# myNucSatellite.net
KiCad netlist of a schematic drawn in EAGLE
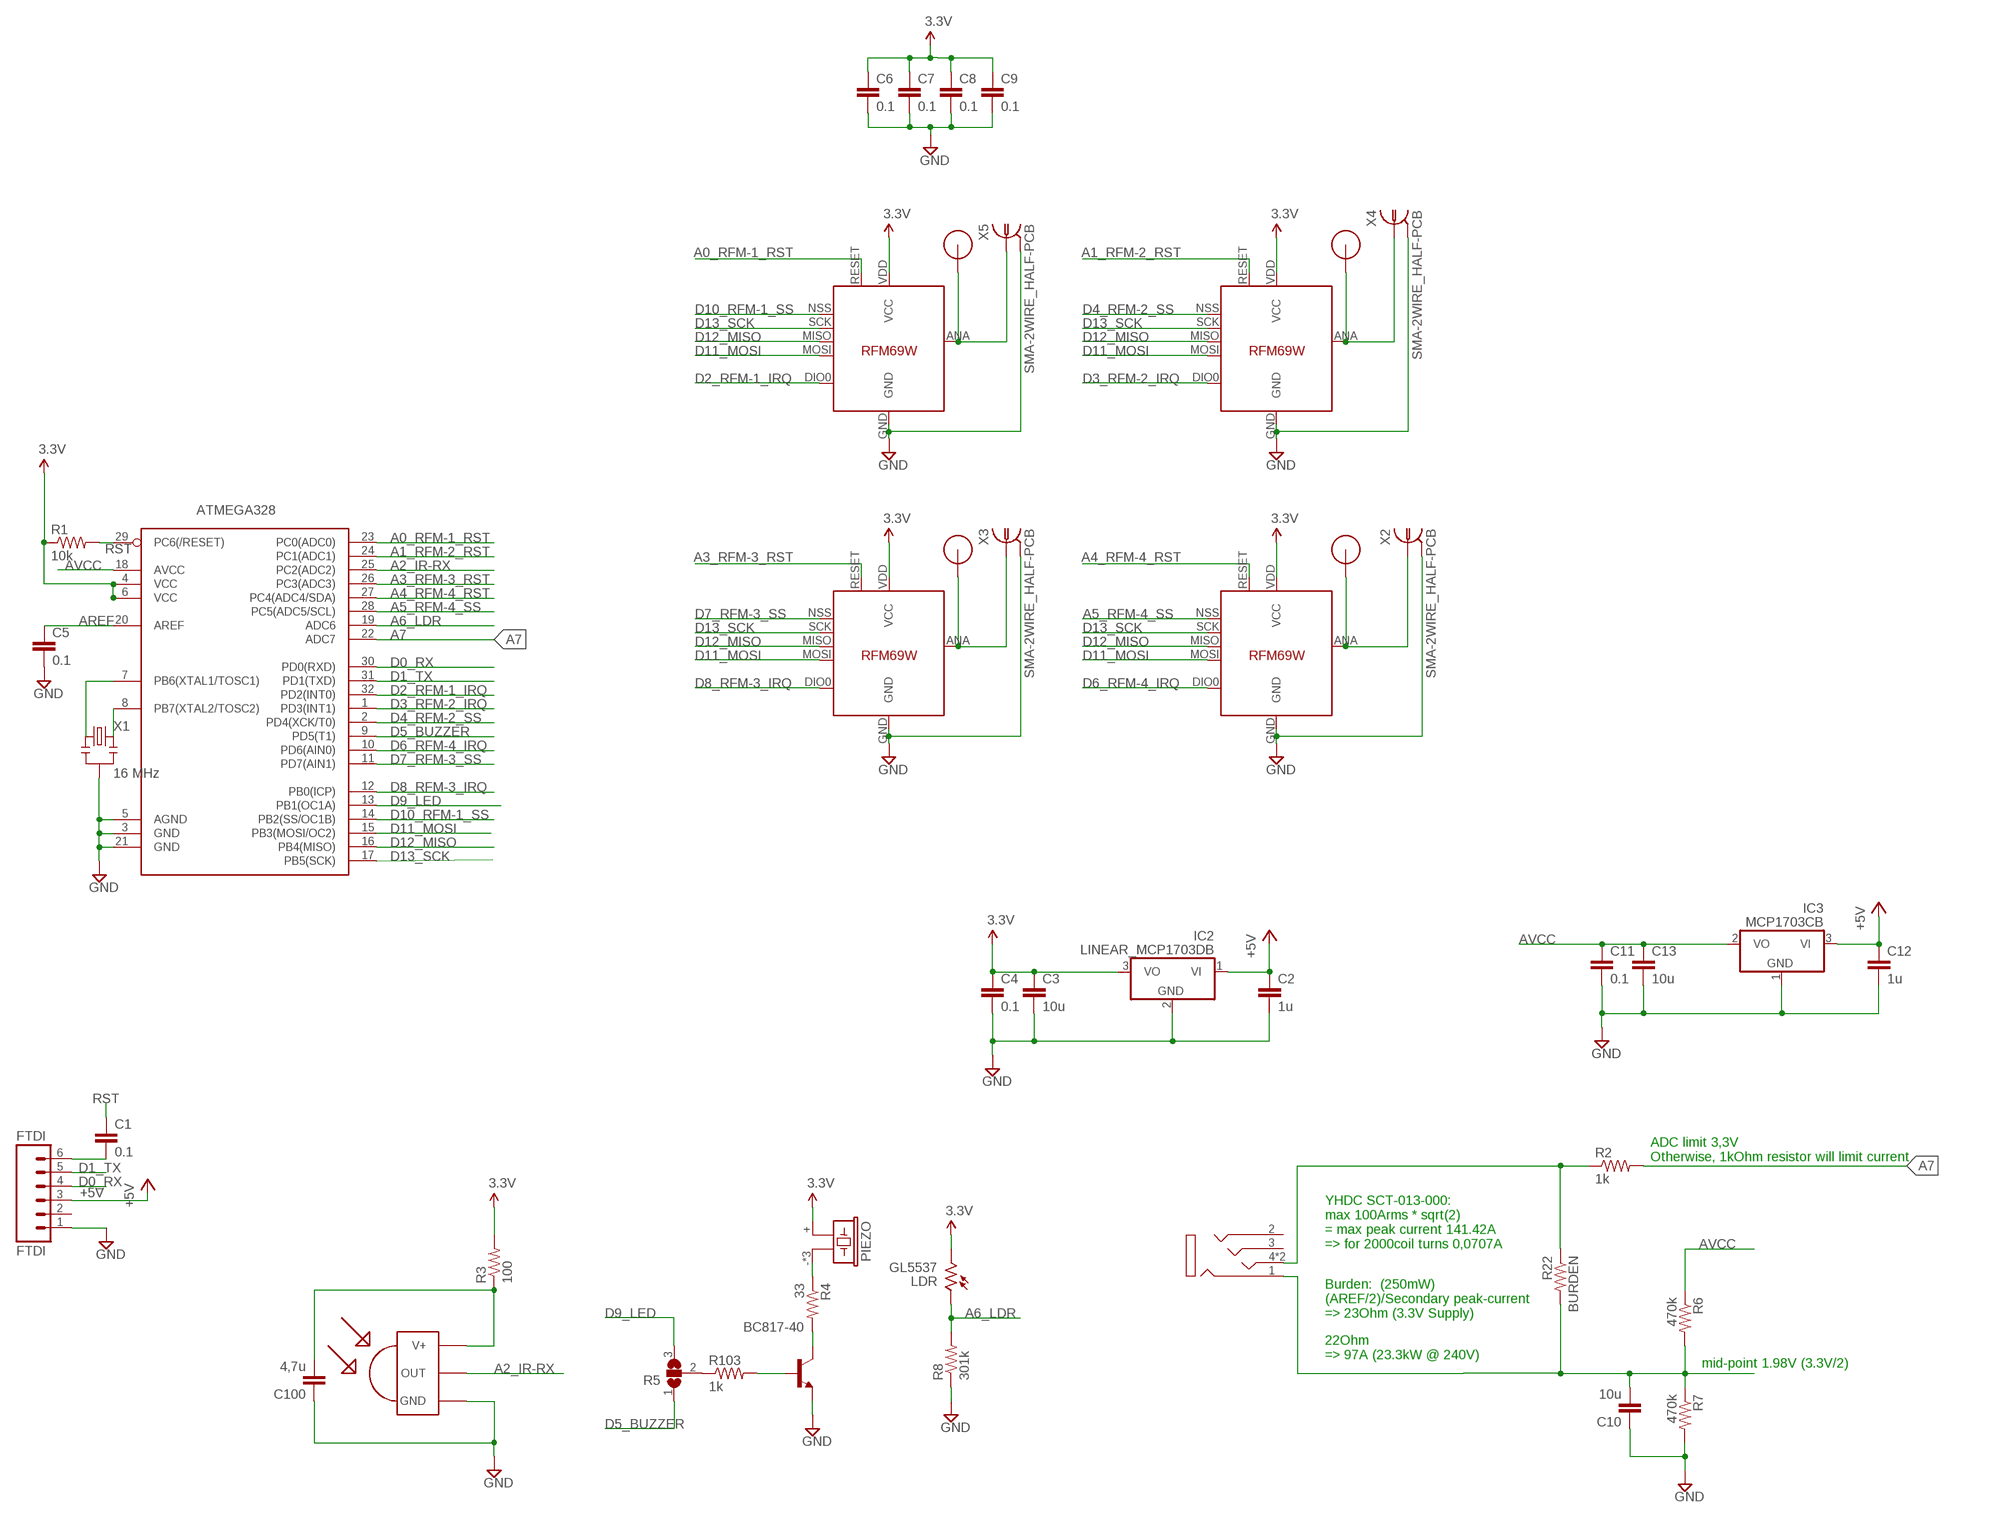
[diagram p0: schematic, sheet 1]

(export (version "E")
  (design (tool "Eeschema 10.0.6"))
  (components
    (comp (ref "ATMEGA328")
      (value "ATMega-328")
      (footprint "eagle-import:TQFP32-08")
      (libsource (lib "eagle-import") (part "ATMEGA168/328TQFP32"))
    )
    (comp (ref "BC817-40")
      (value "BC817-40-NPN-SOT23-BEC")
      (footprint "eagle-import:SOT23-BEC")
      (libsource (lib "eagle-import") (part "-NPN-SOT23-BECBC817-40"))
    )
    (comp (ref "BURDEN")
      (value "R22")
      (footprint "eagle-import:R0805")
      (libsource (lib "eagle-import") (part "R-US_R0805"))
    )
    (comp (ref "C1")
      (value "0.1")
      (footprint "eagle-import:0603-CAP")
      (libsource (lib "eagle-import") (part "CAP0603-CAP"))
    )
    (comp (ref "C2")
      (value "1u")
      (footprint "eagle-import:0603-CAP")
      (libsource (lib "eagle-import") (part "CAP0603-CAP"))
    )
    (comp (ref "C3")
      (value "10u")
      (footprint "eagle-import:0805-CAP")
      (libsource (lib "eagle-import") (part "myLib_CAP0805-CAP"))
    )
    (comp (ref "C4")
      (value "0.1")
      (footprint "eagle-import:0603-CAP")
      (libsource (lib "eagle-import") (part "CAP0603-CAP"))
    )
    (comp (ref "C5")
      (value "0.1")
      (footprint "eagle-import:0603-CAP")
      (libsource (lib "eagle-import") (part "CAP0603-CAP"))
    )
    (comp (ref "C6")
      (value "0.1")
      (footprint "eagle-import:0603-CAP")
      (libsource (lib "eagle-import") (part "CAP0603-CAP"))
    )
    (comp (ref "C7")
      (value "0.1")
      (footprint "eagle-import:0603-CAP")
      (libsource (lib "eagle-import") (part "CAP0603-CAP"))
    )
    (comp (ref "C8")
      (value "0.1")
      (footprint "eagle-import:0603-CAP")
      (libsource (lib "eagle-import") (part "CAP0603-CAP"))
    )
    (comp (ref "C9")
      (value "0.1")
      (footprint "eagle-import:0603-CAP")
      (libsource (lib "eagle-import") (part "CAP0603-CAP"))
    )
    (comp (ref "C10")
      (value "10u")
      (footprint "eagle-import:0603-CAP")
      (libsource (lib "eagle-import") (part "CAP0603-CAP"))
    )
    (comp (ref "C11")
      (value "0.1")
      (footprint "eagle-import:0603-CAP")
      (libsource (lib "eagle-import") (part "CAP0603-CAP"))
    )
    (comp (ref "C12")
      (value "1u")
      (footprint "eagle-import:0603-CAP")
      (libsource (lib "eagle-import") (part "CAP0603-CAP"))
    )
    (comp (ref "C13")
      (value "10u")
      (footprint "eagle-import:0805-CAP")
      (libsource (lib "eagle-import") (part "myLib_CAP0805-CAP"))
    )
    (comp (ref "C100")
      (value "4,7u")
      (footprint "eagle-import:0603-CAP")
      (libsource (lib "eagle-import") (part "CAP0603-CAP"))
    )
    (comp (ref "CT1")
      (value "1503_13")
      (footprint "eagle-import:1503-03")
      (libsource (lib "eagle-import") (part "1503_13"))
    )
    (comp (ref "FTDI")
      (value "FTDI")
      (footprint "eagle-import:1X06")
      (libsource (lib "eagle-import") (part "M06SIP"))
    )
    (comp (ref "IC2")
      (value "LINEAR_MCP1703DB")
      (footprint "eagle-import:LINEAR_SOT223")
      (libsource (lib "eagle-import") (part "LINEAR_MCP1703DB"))
    )
    (comp (ref "IC3")
      (value "MCP1703CB")
      (footprint "eagle-import:SOT23")
      (libsource (lib "eagle-import") (part "MCP1703CB"))
    )
    (comp (ref "IR-RX")
      (value "TSOP4836")
      (footprint "eagle-import:TSOP18XX")
      (libsource (lib "eagle-import") (part "TSOP4836"))
    )
    (comp (ref "LDR")
      (value "GL5537")
      (footprint "eagle-import:M9960")
      (libsource (lib "eagle-import") (part "M9960_11A"))
    )
    (comp (ref "PIEZO")
      (value "BUZZER-PIEZO_SMD")
      (footprint "eagle-import:BUZZER-PIEZO_SMD")
      (libsource (lib "eagle-import") (part "BUZZER-PIEZO_SMD"))
    )
    (comp (ref "R1")
      (value "10k")
      (footprint "eagle-import:0603-RES")
      (libsource (lib "eagle-import") (part "RESISTOR0603-RES"))
    )
    (comp (ref "R2")
      (value "1k")
      (footprint "eagle-import:0603-RES")
      (libsource (lib "eagle-import") (part "RESISTOR0603-RES"))
    )
    (comp (ref "R3")
      (value "100")
      (footprint "eagle-import:0603-RES")
      (libsource (lib "eagle-import") (part "RESISTOR0603-RES"))
    )
    (comp (ref "R4")
      (value "33")
      (footprint "eagle-import:0603-RES")
      (libsource (lib "eagle-import") (part "RESISTOR0603-RES"))
    )
    (comp (ref "R5")
      (value "SELECT0603-SELECT")
      (footprint "eagle-import:0603-SELECT")
      (libsource (lib "eagle-import") (part "SELECT0603-SELECT"))
    )
    (comp (ref "R6")
      (value "470k")
      (footprint "eagle-import:0603-RES")
      (libsource (lib "eagle-import") (part "RESISTOR0603-RES"))
    )
    (comp (ref "R7")
      (value "470k")
      (footprint "eagle-import:0603-RES")
      (libsource (lib "eagle-import") (part "RESISTOR0603-RES"))
    )
    (comp (ref "R8")
      (value "301k")
      (footprint "eagle-import:0603-RES")
      (libsource (lib "eagle-import") (part "RESISTOR0603-RES"))
    )
    (comp (ref "R103")
      (value "1k")
      (footprint "eagle-import:0603-RES")
      (libsource (lib "eagle-import") (part "RESISTOR0603-RES"))
    )
    (comp (ref "U$3")
      (value "RFM12B_ANTENNA")
      (footprint "eagle-import:RFM12B-ANTENNA")
      (libsource (lib "eagle-import") (part "RFM12B_ANTENNA"))
    )
    (comp (ref "U$4")
      (value "RFM69_MINIPADS")
      (footprint "eagle-import:RFM69W-MINPADS")
      (libsource (lib "eagle-import") (part "RFM69_MINIPADS"))
    )
    (comp (ref "U$6")
      (value "RFM12B_ANTENNA")
      (footprint "eagle-import:RFM12B-ANTENNA")
      (libsource (lib "eagle-import") (part "RFM12B_ANTENNA"))
    )
    (comp (ref "U$7")
      (value "RFM69_MINIPADS")
      (footprint "eagle-import:RFM69W-MINPADS")
      (libsource (lib "eagle-import") (part "RFM69_MINIPADS"))
    )
    (comp (ref "U$8")
      (value "RFM12B_ANTENNA")
      (footprint "eagle-import:RFM12B-ANTENNA")
      (libsource (lib "eagle-import") (part "RFM12B_ANTENNA"))
    )
    (comp (ref "U$9")
      (value "RFM69_MINIPADS")
      (footprint "eagle-import:RFM69W-MINPADS")
      (libsource (lib "eagle-import") (part "RFM69_MINIPADS"))
    )
    (comp (ref "U$10")
      (value "RFM12B_ANTENNA")
      (footprint "eagle-import:RFM12B-ANTENNA")
      (libsource (lib "eagle-import") (part "RFM12B_ANTENNA"))
    )
    (comp (ref "U$11")
      (value "RFM69_MINIPADS")
      (footprint "eagle-import:RFM69W-MINPADS")
      (libsource (lib "eagle-import") (part "RFM69_MINIPADS"))
    )
    (comp (ref "X1")
      (value "16 MHz")
      (footprint "eagle-import:RESONATOR-SMD")
      (libsource (lib "eagle-import") (part "RESONATORSMD"))
    )
    (comp (ref "X2")
      (value "SMA-2WIRE_HALF-PCB")
      (footprint "eagle-import:SMA-EDGE-HALF")
      (libsource (lib "eagle-import") (part "SMA-2WIRE_HALF-PCB"))
    )
    (comp (ref "X3")
      (value "SMA-2WIRE_HALF-PCB")
      (footprint "eagle-import:SMA-EDGE-HALF")
      (libsource (lib "eagle-import") (part "SMA-2WIRE_HALF-PCB"))
    )
    (comp (ref "X4")
      (value "SMA-2WIRE_HALF-PCB")
      (footprint "eagle-import:SMA-EDGE-HALF")
      (libsource (lib "eagle-import") (part "SMA-2WIRE_HALF-PCB"))
    )
    (comp (ref "X5")
      (value "SMA-2WIRE_HALF-PCB")
      (footprint "eagle-import:SMA-EDGE-HALF")
      (libsource (lib "eagle-import") (part "SMA-2WIRE_HALF-PCB"))
    )
  )
  (nets
    (net (code "1") (name "+5V") (class "Default")
      (node (ref "C12") (pin "1") (pinfunction "1_1") (pintype "passive"))
      (node (ref "C2") (pin "1") (pinfunction "1_1") (pintype "passive"))
      (node (ref "FTDI") (pin "3") (pinfunction "3_3") (pintype "passive"))
      (node (ref "IC2") (pin "1") (pinfunction "VI_1") (pintype "input"))
      (node (ref "IC3") (pin "3") (pinfunction "VI_3") (pintype "input"))
    )
    (net (code "2") (name "/A0_RFM-1_RST") (class "Default")
      (node (ref "ATMEGA328") (pin "23") (pinfunction "PC0(ADC0)_23") (pintype "bidirectional"))
      (node (ref "U$4") (pin "RESET") (pinfunction "RESET_RESET") (pintype "input"))
    )
    (net (code "3") (name "/A1_RFM-2_RST") (class "Default")
      (node (ref "ATMEGA328") (pin "24") (pinfunction "PC1(ADC1)_24") (pintype "bidirectional"))
      (node (ref "U$7") (pin "RESET") (pinfunction "RESET_RESET") (pintype "input"))
    )
    (net (code "4") (name "/A2_IR-RX") (class "Default")
      (node (ref "ATMEGA328") (pin "25") (pinfunction "PC2(ADC2)_25") (pintype "bidirectional"))
      (node (ref "IR-RX") (pin "OUT") (pinfunction "OUT_OUT") (pintype "bidirectional"))
    )
    (net (code "5") (name "/A3_RFM-3_RST") (class "Default")
      (node (ref "ATMEGA328") (pin "26") (pinfunction "PC3(ADC3)_26") (pintype "bidirectional"))
      (node (ref "U$9") (pin "RESET") (pinfunction "RESET_RESET") (pintype "input"))
    )
    (net (code "6") (name "/A4_RFM-4_RST") (class "Default")
      (node (ref "ATMEGA328") (pin "27") (pinfunction "PC4(ADC4/SDA)_27") (pintype "bidirectional"))
      (node (ref "U$11") (pin "RESET") (pinfunction "RESET_RESET") (pintype "input"))
    )
    (net (code "7") (name "/A5_RFM-4_SS") (class "Default")
      (node (ref "ATMEGA328") (pin "28") (pinfunction "PC5(ADC5/SCL)_28") (pintype "bidirectional"))
      (node (ref "U$11") (pin "NSS") (pinfunction "SEL_NSS") (pintype "input"))
    )
    (net (code "8") (name "/A6_LDR") (class "Default")
      (node (ref "ATMEGA328") (pin "19") (pinfunction "ADC6_19") (pintype "bidirectional"))
      (node (ref "LDR") (pin "1") (pinfunction "1_1") (pintype "passive"))
      (node (ref "R8") (pin "2") (pinfunction "2_2") (pintype "passive"))
    )
    (net (code "9") (name "/AREF") (class "Default")
      (node (ref "ATMEGA328") (pin "20") (pinfunction "AREF_20") (pintype "bidirectional"))
      (node (ref "C5") (pin "1") (pinfunction "1_1") (pintype "passive"))
    )
    (net (code "10") (name "/AVCC") (class "Default")
      (node (ref "ATMEGA328") (pin "18") (pinfunction "AVCC_18") (pintype "bidirectional"))
      (node (ref "C11") (pin "1") (pinfunction "1_1") (pintype "passive"))
      (node (ref "C13") (pin "1") (pinfunction "1_1") (pintype "passive"))
      (node (ref "IC3") (pin "2") (pinfunction "VO_2") (pintype "passive"))
      (node (ref "R6") (pin "1") (pinfunction "1_1") (pintype "passive"))
    )
    (net (code "11") (name "/D0_RX") (class "Default")
      (node (ref "ATMEGA328") (pin "30") (pinfunction "PD0(RXD)_30") (pintype "bidirectional"))
      (node (ref "FTDI") (pin "4") (pinfunction "4_4") (pintype "passive"))
    )
    (net (code "12") (name "/D1_TX") (class "Default")
      (node (ref "ATMEGA328") (pin "31") (pinfunction "PD1(TXD)_31") (pintype "bidirectional"))
      (node (ref "FTDI") (pin "5") (pinfunction "5_5") (pintype "passive"))
    )
    (net (code "13") (name "/D2_RFM-1_IRQ") (class "Default")
      (node (ref "ATMEGA328") (pin "32") (pinfunction "PD2(INT0)_32") (pintype "bidirectional"))
      (node (ref "U$4") (pin "DIO0") (pinfunction "DIO0/IRQ_DIO0") (pintype "open_collector"))
    )
    (net (code "14") (name "/D3_RFM-2_IRQ") (class "Default")
      (node (ref "ATMEGA328") (pin "1") (pinfunction "PD3(INT1)_1") (pintype "bidirectional"))
      (node (ref "U$7") (pin "DIO0") (pinfunction "DIO0/IRQ_DIO0") (pintype "open_collector"))
    )
    (net (code "15") (name "/D4_RFM-2_SS") (class "Default")
      (node (ref "ATMEGA328") (pin "2") (pinfunction "PD4(XCK/T0)_2") (pintype "bidirectional"))
      (node (ref "U$7") (pin "NSS") (pinfunction "SEL_NSS") (pintype "input"))
    )
    (net (code "16") (name "/D5_BUZZER") (class "Default")
      (node (ref "ATMEGA328") (pin "9") (pinfunction "PD5(T1)_9") (pintype "bidirectional"))
      (node (ref "R5") (pin "1") (pinfunction "1_1") (pintype "passive"))
    )
    (net (code "17") (name "/D6_RFM-4_IRQ") (class "Default")
      (node (ref "ATMEGA328") (pin "10") (pinfunction "PD6(AIN0)_10") (pintype "bidirectional"))
      (node (ref "U$11") (pin "DIO0") (pinfunction "DIO0/IRQ_DIO0") (pintype "open_collector"))
    )
    (net (code "18") (name "/D7_RFM-3_SS") (class "Default")
      (node (ref "ATMEGA328") (pin "11") (pinfunction "PD7(AIN1)_11") (pintype "bidirectional"))
      (node (ref "U$9") (pin "NSS") (pinfunction "SEL_NSS") (pintype "input"))
    )
    (net (code "19") (name "/D8_RFM-3_IRQ") (class "Default")
      (node (ref "ATMEGA328") (pin "12") (pinfunction "PB0(ICP)_12") (pintype "bidirectional"))
      (node (ref "U$9") (pin "DIO0") (pinfunction "DIO0/IRQ_DIO0") (pintype "open_collector"))
    )
    (net (code "20") (name "/D9_LED") (class "Default")
      (node (ref "ATMEGA328") (pin "13") (pinfunction "PB1(OC1A)_13") (pintype "bidirectional"))
      (node (ref "R5") (pin "3") (pinfunction "3_3") (pintype "passive"))
    )
    (net (code "21") (name "/D10_RFM-1_SS") (class "Default")
      (node (ref "ATMEGA328") (pin "14") (pinfunction "PB2(SS/OC1B)_14") (pintype "bidirectional"))
      (node (ref "U$4") (pin "NSS") (pinfunction "SEL_NSS") (pintype "input"))
    )
    (net (code "22") (name "/D11_MOSI") (class "Default")
      (node (ref "ATMEGA328") (pin "15") (pinfunction "PB3(MOSI/OC2)_15") (pintype "bidirectional"))
      (node (ref "U$11") (pin "MOSI") (pinfunction "MOSI_MOSI") (pintype "output"))
      (node (ref "U$4") (pin "MOSI") (pinfunction "MOSI_MOSI") (pintype "output"))
      (node (ref "U$7") (pin "MOSI") (pinfunction "MOSI_MOSI") (pintype "output"))
      (node (ref "U$9") (pin "MOSI") (pinfunction "MOSI_MOSI") (pintype "output"))
    )
    (net (code "23") (name "/D12_MISO") (class "Default")
      (node (ref "ATMEGA328") (pin "16") (pinfunction "PB4(MISO)_16") (pintype "bidirectional"))
      (node (ref "U$11") (pin "MISO") (pinfunction "MISO_MISO") (pintype "input"))
      (node (ref "U$4") (pin "MISO") (pinfunction "MISO_MISO") (pintype "input"))
      (node (ref "U$7") (pin "MISO") (pinfunction "MISO_MISO") (pintype "input"))
      (node (ref "U$9") (pin "MISO") (pinfunction "MISO_MISO") (pintype "input"))
    )
    (net (code "24") (name "/D13_SCK") (class "Default")
      (node (ref "ATMEGA328") (pin "17") (pinfunction "PB5(SCK)_17") (pintype "bidirectional"))
      (node (ref "U$11") (pin "SCK") (pinfunction "SCK_SCK") (pintype "input"))
      (node (ref "U$4") (pin "SCK") (pinfunction "SCK_SCK") (pintype "input"))
      (node (ref "U$7") (pin "SCK") (pinfunction "SCK_SCK") (pintype "input"))
      (node (ref "U$9") (pin "SCK") (pinfunction "SCK_SCK") (pintype "input"))
    )
    (net (code "25") (name "/RST") (class "Default")
      (node (ref "ATMEGA328") (pin "29") (pinfunction "PC6(/RESET)_29") (pintype "bidirectional"))
      (node (ref "C1") (pin "1") (pinfunction "1_1") (pintype "passive"))
      (node (ref "R1") (pin "2") (pinfunction "2_2") (pintype "passive"))
    )
    (net (code "26") (name "3.3V") (class "Default")
      (node (ref "ATMEGA328") (pin "4") (pinfunction "VCC_4") (pintype "bidirectional"))
      (node (ref "ATMEGA328") (pin "6") (pinfunction "VCC_6") (pintype "bidirectional"))
      (node (ref "C3") (pin "1") (pinfunction "1_1") (pintype "passive"))
      (node (ref "C4") (pin "1") (pinfunction "1_1") (pintype "passive"))
      (node (ref "C6") (pin "1") (pinfunction "1_1") (pintype "passive"))
      (node (ref "C7") (pin "1") (pinfunction "1_1") (pintype "passive"))
      (node (ref "C8") (pin "1") (pinfunction "1_1") (pintype "passive"))
      (node (ref "C9") (pin "1") (pinfunction "1_1") (pintype "passive"))
      (node (ref "IC2") (pin "3") (pinfunction "VO_3") (pintype "passive"))
      (node (ref "LDR") (pin "2") (pinfunction "2_2") (pintype "passive"))
      (node (ref "PIEZO") (pin "+") (pinfunction "1_+") (pintype "passive"))
      (node (ref "R1") (pin "1") (pinfunction "1_1") (pintype "passive"))
      (node (ref "R3") (pin "2") (pinfunction "2_2") (pintype "passive"))
      (node (ref "U$11") (pin "VDD") (pinfunction "VCC_VDD") (pintype "power_in"))
      (node (ref "U$4") (pin "VDD") (pinfunction "VCC_VDD") (pintype "power_in"))
      (node (ref "U$7") (pin "VDD") (pinfunction "VCC_VDD") (pintype "power_in"))
      (node (ref "U$9") (pin "VDD") (pinfunction "VCC_VDD") (pintype "power_in"))
    )
    (net (code "27") (name "A7") (class "Default")
      (node (ref "ATMEGA328") (pin "22") (pinfunction "ADC7_22") (pintype "bidirectional"))
      (node (ref "R2") (pin "2") (pinfunction "2_2") (pintype "passive"))
    )
    (net (code "28") (name "GND") (class "Default")
      (node (ref "ATMEGA328") (pin "21") (pinfunction "GND_21") (pintype "bidirectional"))
      (node (ref "ATMEGA328") (pin "3") (pinfunction "GND_3") (pintype "bidirectional"))
      (node (ref "ATMEGA328") (pin "5") (pinfunction "AGND_5") (pintype "bidirectional"))
      (node (ref "BC817-40") (pin "E") (pinfunction "E_E") (pintype "passive"))
      (node (ref "C10") (pin "1") (pinfunction "1_1") (pintype "passive"))
      (node (ref "C100") (pin "1") (pinfunction "1_1") (pintype "passive"))
      (node (ref "C11") (pin "2") (pinfunction "2_2") (pintype "passive"))
      (node (ref "C12") (pin "2") (pinfunction "2_2") (pintype "passive"))
      (node (ref "C13") (pin "2") (pinfunction "2_2") (pintype "passive"))
      (node (ref "C2") (pin "2") (pinfunction "2_2") (pintype "passive"))
      (node (ref "C3") (pin "2") (pinfunction "2_2") (pintype "passive"))
      (node (ref "C4") (pin "2") (pinfunction "2_2") (pintype "passive"))
      (node (ref "C5") (pin "2") (pinfunction "2_2") (pintype "passive"))
      (node (ref "C6") (pin "2") (pinfunction "2_2") (pintype "passive"))
      (node (ref "C7") (pin "2") (pinfunction "2_2") (pintype "passive"))
      (node (ref "C8") (pin "2") (pinfunction "2_2") (pintype "passive"))
      (node (ref "C9") (pin "2") (pinfunction "2_2") (pintype "passive"))
      (node (ref "FTDI") (pin "1") (pinfunction "1_1") (pintype "passive"))
      (node (ref "IC2") (pin "2") (pinfunction "GND_2") (pintype "passive"))
      (node (ref "IC3") (pin "1") (pinfunction "GND_1") (pintype "passive"))
      (node (ref "IR-RX") (pin "GND") (pinfunction "GND_GND") (pintype "bidirectional"))
      (node (ref "R7") (pin "2") (pinfunction "2_2") (pintype "passive"))
      (node (ref "R8") (pin "1") (pinfunction "1_1") (pintype "passive"))
      (node (ref "U$11") (pin "GND") (pinfunction "GND_GND") (pintype "power_in"))
      (node (ref "U$4") (pin "GND") (pinfunction "GND_GND") (pintype "power_in"))
      (node (ref "U$7") (pin "GND") (pinfunction "GND_GND") (pintype "power_in"))
      (node (ref "U$9") (pin "GND") (pinfunction "GND_GND") (pintype "power_in"))
      (node (ref "X1") (pin "2") (pinfunction "2_2") (pintype "passive"))
      (node (ref "X2") (pin "GND@0") (pinfunction "GND_GND@0") (pintype "passive"))
      (node (ref "X2") (pin "GND@1") (pinfunction "GND_GND@1") (pintype "passive"))
      (node (ref "X3") (pin "GND@0") (pinfunction "GND_GND@0") (pintype "passive"))
      (node (ref "X3") (pin "GND@1") (pinfunction "GND_GND@1") (pintype "passive"))
      (node (ref "X4") (pin "GND@0") (pinfunction "GND_GND@0") (pintype "passive"))
      (node (ref "X4") (pin "GND@1") (pinfunction "GND_GND@1") (pintype "passive"))
      (node (ref "X5") (pin "GND@0") (pinfunction "GND_GND@0") (pintype "passive"))
      (node (ref "X5") (pin "GND@1") (pinfunction "GND_GND@1") (pintype "passive"))
    )
    (net (code "29") (name "Net-(ATMEGA328-PB6(XTAL1{slash}TOSC1))") (class "Default")
      (node (ref "ATMEGA328") (pin "7") (pinfunction "PB6(XTAL1/TOSC1)_7") (pintype "bidirectional"))
      (node (ref "X1") (pin "1") (pinfunction "1_1") (pintype "passive"))
    )
    (net (code "30") (name "Net-(ATMEGA328-PB7(XTAL2{slash}TOSC2))") (class "Default")
      (node (ref "ATMEGA328") (pin "8") (pinfunction "PB7(XTAL2/TOSC2)_8") (pintype "bidirectional"))
      (node (ref "X1") (pin "3") (pinfunction "3_3") (pintype "passive"))
    )
    (net (code "31") (name "Net-(BC817-40-PadB)") (class "Default")
      (node (ref "BC817-40") (pin "B") (pinfunction "B_B") (pintype "passive"))
      (node (ref "R103") (pin "2") (pinfunction "2_2") (pintype "passive"))
    )
    (net (code "32") (name "Net-(BC817-40-PadC)") (class "Default")
      (node (ref "BC817-40") (pin "C") (pinfunction "C_C") (pintype "passive"))
      (node (ref "R4") (pin "2") (pinfunction "2_2") (pintype "passive"))
    )
    (net (code "33") (name "Net-(BURDEN-Pad1)") (class "Default")
      (node (ref "BURDEN") (pin "1") (pinfunction "1_1") (pintype "passive"))
      (node (ref "CT1") (pin "4") (pinfunction "4_4") (pintype "bidirectional"))
      (node (ref "CT1") (pin "4-2") (pinfunction "4_4-2") (pintype "bidirectional"))
      (node (ref "R2") (pin "1") (pinfunction "1_1") (pintype "passive"))
    )
    (net (code "34") (name "Net-(BURDEN-Pad2)") (class "Default")
      (node (ref "BURDEN") (pin "2") (pinfunction "2_2") (pintype "passive"))
      (node (ref "C10") (pin "2") (pinfunction "2_2") (pintype "passive"))
      (node (ref "CT1") (pin "1") (pinfunction "1_1") (pintype "bidirectional"))
      (node (ref "R6") (pin "2") (pinfunction "2_2") (pintype "passive"))
      (node (ref "R7") (pin "1") (pinfunction "1_1") (pintype "passive"))
    )
    (net (code "35") (name "Net-(C1-Pad2)") (class "Default")
      (node (ref "C1") (pin "2") (pinfunction "2_2") (pintype "passive"))
      (node (ref "FTDI") (pin "6") (pinfunction "6_6") (pintype "passive"))
    )
    (net (code "36") (name "Net-(IR-RX-V+)") (class "Default")
      (node (ref "C100") (pin "2") (pinfunction "2_2") (pintype "passive"))
      (node (ref "IR-RX") (pin "VCC") (pinfunction "V+_VCC") (pintype "bidirectional"))
      (node (ref "R3") (pin "1") (pinfunction "1_1") (pintype "passive"))
    )
    (net (code "37") (name "Net-(PIEZO-2-Pad-)") (class "Default")
      (node (ref "PIEZO") (pin "-") (pinfunction "2_-") (pintype "passive"))
      (node (ref "PIEZO") (pin "DUMMY") (pinfunction "2_DUMMY") (pintype "passive"))
      (node (ref "PIEZO") (pin "DUMMY1") (pinfunction "2_DUMMY1") (pintype "passive"))
      (node (ref "R4") (pin "1") (pinfunction "1_1") (pintype "passive"))
    )
    (net (code "38") (name "Net-(R103-Pad1)") (class "Default")
      (node (ref "R103") (pin "1") (pinfunction "1_1") (pintype "passive"))
      (node (ref "R5") (pin "2") (pinfunction "2_2") (pintype "passive"))
    )
    (net (code "39") (name "Net-(U$3-1)") (class "Default")
      (node (ref "U$3") (pin "P$1") (pinfunction "1_P$1") (pintype "bidirectional"))
      (node (ref "U$4") (pin "ANA") (pinfunction "ANT_ANA") (pintype "passive"))
      (node (ref "X5") (pin "SIG") (pinfunction "SIGNAL_SIG") (pintype "passive"))
    )
    (net (code "40") (name "Net-(U$6-1)") (class "Default")
      (node (ref "U$6") (pin "P$1") (pinfunction "1_P$1") (pintype "bidirectional"))
      (node (ref "U$7") (pin "ANA") (pinfunction "ANT_ANA") (pintype "passive"))
      (node (ref "X4") (pin "SIG") (pinfunction "SIGNAL_SIG") (pintype "passive"))
    )
    (net (code "41") (name "Net-(U$8-1)") (class "Default")
      (node (ref "U$8") (pin "P$1") (pinfunction "1_P$1") (pintype "bidirectional"))
      (node (ref "U$9") (pin "ANA") (pinfunction "ANT_ANA") (pintype "passive"))
      (node (ref "X3") (pin "SIG") (pinfunction "SIGNAL_SIG") (pintype "passive"))
    )
    (net (code "42") (name "Net-(U$10-1)") (class "Default")
      (node (ref "U$10") (pin "P$1") (pinfunction "1_P$1") (pintype "bidirectional"))
      (node (ref "U$11") (pin "ANA") (pinfunction "ANT_ANA") (pintype "passive"))
      (node (ref "X2") (pin "SIG") (pinfunction "SIGNAL_SIG") (pintype "passive"))
    )
    (net (code "43") (name "unconnected-(CT1-Pad2)") (class "Default")
      (node (ref "CT1") (pin "2") (pinfunction "2_2") (pintype "bidirectional"))
    )
    (net (code "44") (name "unconnected-(CT1-Pad3)") (class "Default")
      (node (ref "CT1") (pin "3") (pinfunction "3_3") (pintype "bidirectional"))
    )
    (net (code "45") (name "unconnected-(FTDI-Pad2)") (class "Default")
      (node (ref "FTDI") (pin "2") (pinfunction "2_2") (pintype "passive"))
    )
  )
)
